# RS485.net
KiCad netlist of a schematic drawn in Altium Designer
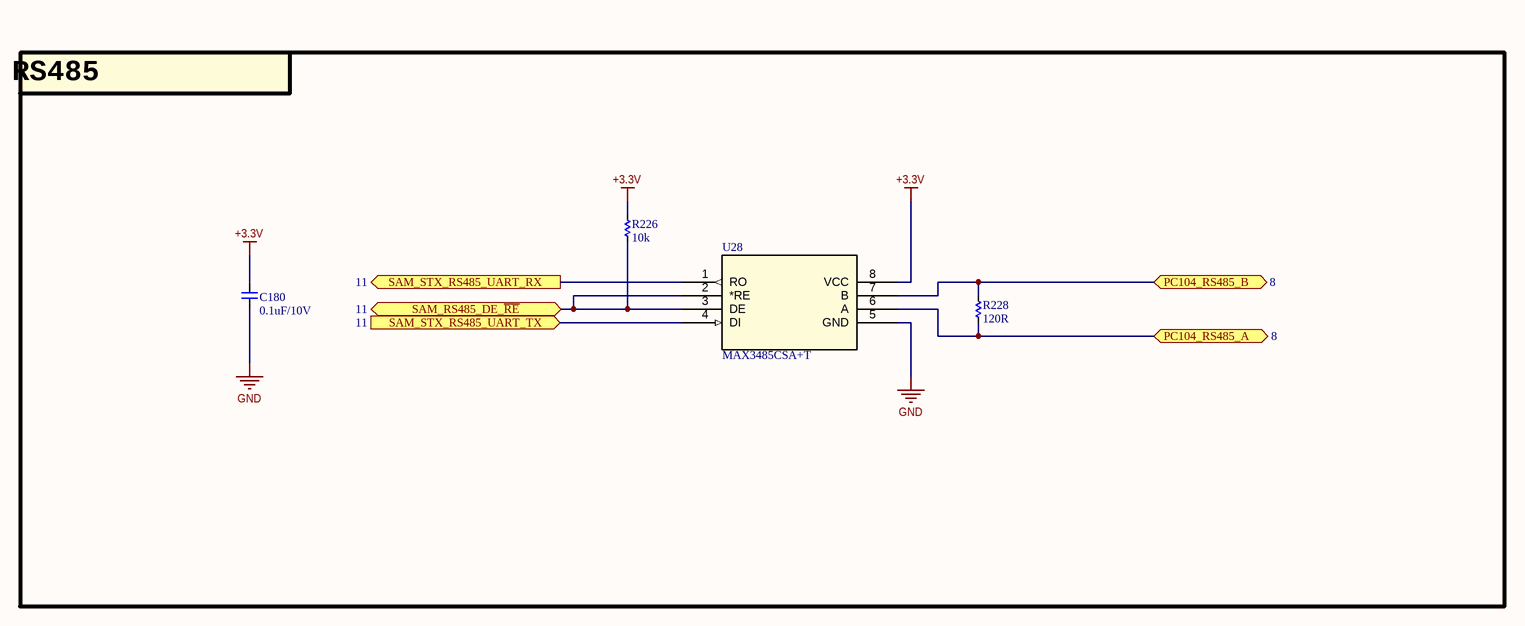
[diagram p0: RS485.SchDoc]

(export (version "E")
  (design (tool "Eeschema 10.0.6"))
  (components
    (comp (ref "C180")
      (value "0.1uF/10V")
      (footprint "CAP_C_1005X50_L")
      (description "CAP")
      (libsource (lib "LABLIB") (part "_CAP_C_2"))
    )
    (comp (ref "R226")
      (value "10k")
      (footprint "RES_C_1005x30_L")
      (description "RES")
      (libsource (lib "LABLIB") (part "_RES_B_2"))
    )
    (comp (ref "R228")
      (value "120R")
      (footprint "RES_C_1005x30_L")
      (description "RES")
      (libsource (lib "IFBschelib") (part "_RES_B_2"))
    )
    (comp (ref "U28")
      (value "MAX3485CSA+T")
      (footprint "21-0041-3-M_90-0096-8L_MXM")
      (description "Low-Power, Slew-Rate-Limited RS-485/RS-422 Transceivers, IC TRANSCEIVER HALF 1/1 8SOIC")
      (fields
        (field (name "MANUFACTURER_PART_NUMBER") "MAX485CSA+T")
        (field (name "COPYRIGHT") "Copyright (C) 2025 Ultra Librarian. All rights reserved.")
      )
      (libsource (lib "IFBschelib") (part "MAX3485CSA+T"))
    )
  )
  (nets
    (net (code "1") (name "+3.3V") (class "Default")
      (node (ref "C180") (pin "2") (pinfunction "2_2") (pintype "passive"))
      (node (ref "R226") (pin "1") (pinfunction "1_1") (pintype "passive"))
      (node (ref "U28") (pin "8") (pinfunction "VCC_8") (pintype "power_in"))
    )
    (net (code "2") (name "/PC104_RS485_A") (class "Default")
      (node (ref "R228") (pin "2") (pinfunction "2_2") (pintype "passive"))
      (node (ref "U28") (pin "6") (pinfunction "A_6") (pintype "passive"))
    )
    (net (code "3") (name "/PC104_RS485_B") (class "Default")
      (node (ref "R228") (pin "1") (pinfunction "1_1") (pintype "passive"))
      (node (ref "U28") (pin "7") (pinfunction "B_7") (pintype "passive"))
    )
    (net (code "4") (name "/SAM_RS485_DE_~{RE}") (class "Default")
      (node (ref "R226") (pin "2") (pinfunction "2_2") (pintype "passive"))
      (node (ref "U28") (pin "2") (pinfunction "*RE_2") (pintype "passive"))
      (node (ref "U28") (pin "3") (pinfunction "DE_3") (pintype "passive"))
    )
    (net (code "5") (name "/SAM_STX_RS485_UART_RX") (class "Default")
      (node (ref "U28") (pin "1") (pinfunction "RO_1") (pintype "output"))
    )
    (net (code "6") (name "/SAM_STX_RS485_UART_TX") (class "Default")
      (node (ref "U28") (pin "4") (pinfunction "DI_4") (pintype "input"))
    )
    (net (code "7") (name "GND") (class "Default")
      (node (ref "C180") (pin "1") (pinfunction "1_1") (pintype "passive"))
      (node (ref "U28") (pin "5") (pinfunction "GND_5") (pintype "power_in"))
    )
  )
)
